# mcu.net
KiCad netlist of a schematic drawn in Altium Designer
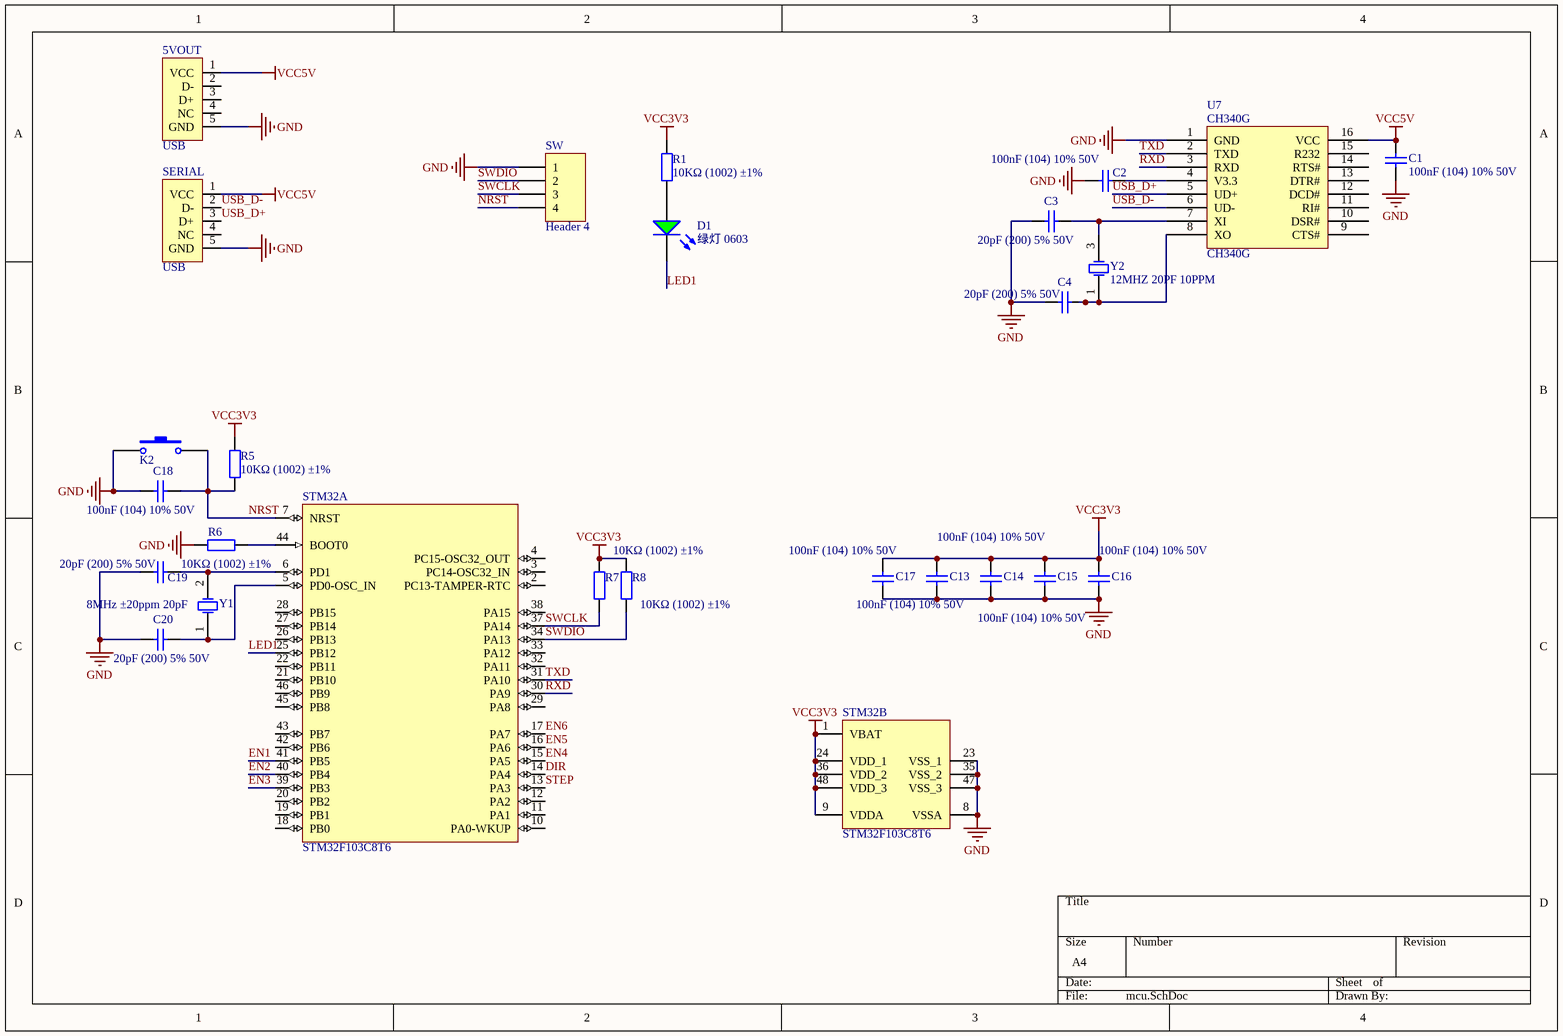
[diagram p0: mcu.SchDoc]

(export (version "E")
  (design (tool "Eeschema 10.0.6"))
  (components
    (comp (ref "5VOUT")
      (value "USB")
      (footprint "USB_5")
      (libsource (lib "Personal_Accumulation_Sch") (part "USB_2"))
    )
    (comp (ref "C1")
      (value "100nF (104) 10% 50V")
      (footprint "0603_C")
      (description "贴片电容")
      (libsource (lib "Miscellaneous Devices LC") (part "0603 100nF (104) 10% 50V"))
    )
    (comp (ref "C2")
      (value "100nF (104) 10% 50V")
      (footprint "0603_C")
      (description "贴片电容")
      (libsource (lib "Miscellaneous Devices LC") (part "0603 100nF (104) 10% 50V"))
    )
    (comp (ref "C3")
      (value "20pF (200) 5% 50V")
      (footprint "0603_C")
      (description "贴片电容")
      (libsource (lib "Miscellaneous Devices LC") (part "0603 20pF (200) 5% 50V"))
    )
    (comp (ref "C4")
      (value "20pF (200) 5% 50V")
      (footprint "0603_C")
      (description "贴片电容")
      (libsource (lib "Miscellaneous Devices LC") (part "0603 20pF (200) 5% 50V"))
    )
    (comp (ref "C13")
      (value "100nF (104) 10% 50V")
      (footprint "0603_C")
      (description "贴片电容")
      (libsource (lib "Miscellaneous Devices LC") (part "0603 100nF (104) 10% 50V"))
    )
    (comp (ref "C14")
      (value "100nF (104) 10% 50V")
      (footprint "0603_C")
      (description "贴片电容")
      (libsource (lib "Miscellaneous Devices LC") (part "0603 100nF (104) 10% 50V"))
    )
    (comp (ref "C15")
      (value "100nF (104) 10% 50V")
      (footprint "0603_C")
      (description "贴片电容")
      (libsource (lib "Miscellaneous Devices LC") (part "0603 100nF (104) 10% 50V"))
    )
    (comp (ref "C16")
      (value "100nF (104) 10% 50V")
      (footprint "0603_C")
      (description "贴片电容")
      (libsource (lib "Miscellaneous Devices LC") (part "0603 100nF (104) 10% 50V"))
    )
    (comp (ref "C17")
      (value "100nF (104) 10% 50V")
      (footprint "0603_C")
      (description "贴片电容")
      (libsource (lib "Miscellaneous Devices LC") (part "0603 100nF (104) 10% 50V"))
    )
    (comp (ref "C18")
      (value "100nF (104) 10% 50V")
      (footprint "0603_C")
      (description "贴片电容")
      (libsource (lib "Miscellaneous Devices LC") (part "0603 100nF (104) 10% 50V"))
    )
    (comp (ref "C19")
      (value "20pF (200) 5% 50V")
      (footprint "0603_C")
      (description "贴片电容")
      (libsource (lib "Miscellaneous Devices LC") (part "0603 20pF (200) 5% 50V"))
    )
    (comp (ref "C20")
      (value "20pF (200) 5% 50V")
      (footprint "0603_C")
      (description "贴片电容")
      (libsource (lib "Miscellaneous Devices LC") (part "0603 20pF (200) 5% 50V"))
    )
    (comp (ref "D1")
      (value "绿灯 0603")
      (footprint "0603_LED_S1")
      (description "发光二极管")
      (libsource (lib "Miscellaneous Devices LC") (part "0603 绿灯"))
    )
    (comp (ref "K2")
      (value "KEY")
      (footprint "Key_Sop")
      (description "贴片按键")
      (libsource (lib "Schlib1") (part "KEY_SOP"))
    )
    (comp (ref "R1")
      (value "10KΩ (1002) ±1%")
      (footprint "0603_R")
      (description "贴片电阻")
      (libsource (lib "Miscellaneous Devices LC") (part "0603 10KΩ (1002) 1%"))
    )
    (comp (ref "R5")
      (value "10KΩ (1002) ±1%")
      (footprint "0603_R")
      (description "贴片电阻")
      (libsource (lib "") (part "0603 10KΩ (1002) 1%_1"))
    )
    (comp (ref "R6")
      (value "10KΩ (1002) ±1%")
      (footprint "0603_R")
      (description "贴片电阻")
      (libsource (lib "") (part "0603 10KΩ (1002) 1%_2"))
    )
    (comp (ref "R7")
      (value "10KΩ (1002) ±1%")
      (footprint "0603_R")
      (description "贴片电阻")
      (libsource (lib "") (part "0603 10KΩ (1002) 1%_1"))
    )
    (comp (ref "R8")
      (value "10KΩ (1002) ±1%")
      (footprint "0603_R")
      (description "贴片电阻")
      (libsource (lib "") (part "0603 10KΩ (1002) 1%_1"))
    )
    (comp (ref "SERIAL")
      (value "USB")
      (footprint "USB_5")
      (libsource (lib "Personal_Accumulation_Sch") (part "USB_2"))
    )
    (comp (ref "STM32")
      (value "STM32F103C8T6")
      (footprint "LQFP-48_7x7x05P")
      (description "ARM")
      (libsource (lib "Miscellaneous Devices LC") (part "STM32F103C8T6"))
    )
    (comp (ref "SW")
      (value "Header 4")
      (footprint "HDR1X4")
      (description "Header, 4-Pin")
      (fields (field (name "PUBLISHER") "Altium Limited"))
      (libsource (lib "Common Headers") (part "Header 4"))
    )
    (comp (ref "U7")
      (value "CH340G")
      (footprint "SOIC-16_150mil")
      (description "USB")
      (libsource (lib "Miscellaneous Devices LC") (part "CH340G_[C14267]"))
    )
    (comp (ref "Y1")
      (value "8MHz ±20ppm 20pF")
      (footprint "SMD-5032_2P")
      (description "贴片晶振")
      (libsource (lib "Miscellaneous Devices LC") (part "SMD-5032_2P 8MHz 20ppm 20pF"))
    )
    (comp (ref "Y2")
      (value "12MHZ 20PF 10PPM")
      (footprint "SMD-3225_4P")
      (description "贴片晶振")
      (libsource (lib "Miscellaneous Devices LC") (part "SMD-3225_4P  12MHZ 20PF 10PPM"))
    )
  )
  (nets
    (net (code "1") (name "/DIR") (class "Default")
      (node (ref "STM32") (pin "14") (pinfunction "PA4_14") (pintype "bidirectional"))
    )
    (net (code "2") (name "/EN1") (class "Default")
      (node (ref "STM32") (pin "41") (pinfunction "PB5_41") (pintype "bidirectional"))
    )
    (net (code "3") (name "/EN2") (class "Default")
      (node (ref "STM32") (pin "40") (pinfunction "PB4_40") (pintype "bidirectional"))
    )
    (net (code "4") (name "/EN3") (class "Default")
      (node (ref "STM32") (pin "39") (pinfunction "PB3_39") (pintype "bidirectional"))
    )
    (net (code "5") (name "/EN4") (class "Default")
      (node (ref "STM32") (pin "15") (pinfunction "PA5_15") (pintype "bidirectional"))
    )
    (net (code "6") (name "/EN5") (class "Default")
      (node (ref "STM32") (pin "16") (pinfunction "PA6_16") (pintype "bidirectional"))
    )
    (net (code "7") (name "/EN6") (class "Default")
      (node (ref "STM32") (pin "17") (pinfunction "PA7_17") (pintype "bidirectional"))
    )
    (net (code "8") (name "/LED1") (class "Default")
      (node (ref "D1") (pin "K") (pinfunction "K_K") (pintype "passive"))
      (node (ref "STM32") (pin "25") (pinfunction "PB12_25") (pintype "bidirectional"))
    )
    (net (code "9") (name "/NRST") (class "Default")
      (node (ref "C18") (pin "1") (pinfunction "1_1") (pintype "passive"))
      (node (ref "K2") (pin "2") (pinfunction "2_2") (pintype "passive"))
      (node (ref "R5") (pin "1") (pinfunction "1_1") (pintype "passive"))
      (node (ref "STM32") (pin "7") (pinfunction "NRST_7") (pintype "bidirectional"))
      (node (ref "SW") (pin "4") (pinfunction "4_4") (pintype "passive"))
    )
    (net (code "10") (name "/RXD") (class "Default")
      (node (ref "STM32") (pin "30") (pinfunction "PA9_30") (pintype "bidirectional"))
      (node (ref "U7") (pin "3") (pinfunction "RXD_3") (pintype "passive"))
    )
    (net (code "11") (name "/STEP") (class "Default")
      (node (ref "STM32") (pin "13") (pinfunction "PA3_13") (pintype "bidirectional"))
    )
    (net (code "12") (name "/SWCLK") (class "Default")
      (node (ref "R7") (pin "1") (pinfunction "1_1") (pintype "passive"))
      (node (ref "STM32") (pin "37") (pinfunction "PA14_37") (pintype "bidirectional"))
      (node (ref "SW") (pin "3") (pinfunction "3_3") (pintype "passive"))
    )
    (net (code "13") (name "/SWDIO") (class "Default")
      (node (ref "R8") (pin "1") (pinfunction "1_1") (pintype "passive"))
      (node (ref "STM32") (pin "34") (pinfunction "PA13_34") (pintype "bidirectional"))
      (node (ref "SW") (pin "2") (pinfunction "2_2") (pintype "passive"))
    )
    (net (code "14") (name "/TXD") (class "Default")
      (node (ref "STM32") (pin "31") (pinfunction "PA10_31") (pintype "bidirectional"))
      (node (ref "U7") (pin "2") (pinfunction "TXD_2") (pintype "passive"))
    )
    (net (code "15") (name "/USB_D+") (class "Default")
      (node (ref "SERIAL") (pin "3") (pinfunction "D+_3") (pintype "passive"))
      (node (ref "U7") (pin "5") (pinfunction "UD+_5") (pintype "passive"))
    )
    (net (code "16") (name "/USB_D-") (class "Default")
      (node (ref "SERIAL") (pin "2") (pinfunction "D-_2") (pintype "passive"))
      (node (ref "U7") (pin "6") (pinfunction "UD-_6") (pintype "passive"))
    )
    (net (code "17") (name "GND") (class "Default")
      (node (ref "5VOUT") (pin "5") (pinfunction "GND_5") (pintype "passive"))
      (node (ref "C1") (pin "1") (pinfunction "1_1") (pintype "passive"))
      (node (ref "C13") (pin "1") (pinfunction "1_1") (pintype "passive"))
      (node (ref "C14") (pin "1") (pinfunction "1_1") (pintype "passive"))
      (node (ref "C15") (pin "1") (pinfunction "1_1") (pintype "passive"))
      (node (ref "C16") (pin "1") (pinfunction "1_1") (pintype "passive"))
      (node (ref "C17") (pin "1") (pinfunction "1_1") (pintype "passive"))
      (node (ref "C18") (pin "2") (pinfunction "2_2") (pintype "passive"))
      (node (ref "C19") (pin "1") (pinfunction "1_1") (pintype "passive"))
      (node (ref "C2") (pin "1") (pinfunction "1_1") (pintype "passive"))
      (node (ref "C20") (pin "1") (pinfunction "1_1") (pintype "passive"))
      (node (ref "C3") (pin "2") (pinfunction "2_2") (pintype "passive"))
      (node (ref "C4") (pin "2") (pinfunction "2_2") (pintype "passive"))
      (node (ref "K2") (pin "1") (pinfunction "1_1") (pintype "passive"))
      (node (ref "R6") (pin "2") (pinfunction "2_2") (pintype "passive"))
      (node (ref "SERIAL") (pin "5") (pinfunction "GND_5") (pintype "passive"))
      (node (ref "STM32") (pin "23") (pinfunction "VSS_1_23") (pintype "power_in"))
      (node (ref "STM32") (pin "35") (pinfunction "VSS_2_35") (pintype "power_in"))
      (node (ref "STM32") (pin "47") (pinfunction "VSS_3_47") (pintype "power_in"))
      (node (ref "STM32") (pin "8") (pinfunction "VSSA_8") (pintype "power_in"))
      (node (ref "SW") (pin "1") (pinfunction "1_1") (pintype "passive"))
      (node (ref "U7") (pin "1") (pinfunction "GND_1") (pintype "passive"))
    )
    (net (code "18") (name "Net-(D1-PadA)") (class "Default")
      (node (ref "D1") (pin "A") (pinfunction "A_A") (pintype "passive"))
      (node (ref "R1") (pin "2") (pinfunction "2_2") (pintype "passive"))
    )
    (net (code "19") (name "Net-(STM32A-BOOT0)") (class "Default")
      (node (ref "R6") (pin "1") (pinfunction "1_1") (pintype "passive"))
      (node (ref "STM32") (pin "44") (pinfunction "BOOT0_44") (pintype "input"))
    )
    (net (code "20") (name "Net-(STM32A-PD0-OSC_IN)") (class "Default")
      (node (ref "C20") (pin "2") (pinfunction "2_2") (pintype "passive"))
      (node (ref "STM32") (pin "5") (pinfunction "PD0-OSC_IN_5") (pintype "bidirectional"))
      (node (ref "Y1") (pin "1") (pinfunction "OSC1_1") (pintype "passive"))
    )
    (net (code "21") (name "Net-(STM32A-PD1)") (class "Default")
      (node (ref "C19") (pin "2") (pinfunction "2_2") (pintype "passive"))
      (node (ref "STM32") (pin "6") (pinfunction "PD1_6") (pintype "bidirectional"))
      (node (ref "Y1") (pin "2") (pinfunction "OSC2_2") (pintype "passive"))
    )
    (net (code "22") (name "Net-(U7-V3.3)") (class "Default")
      (node (ref "C2") (pin "2") (pinfunction "2_2") (pintype "passive"))
      (node (ref "U7") (pin "4") (pinfunction "V3.3_4") (pintype "passive"))
    )
    (net (code "23") (name "Net-(U7-XI)") (class "Default")
      (node (ref "C3") (pin "1") (pinfunction "1_1") (pintype "passive"))
      (node (ref "U7") (pin "7") (pinfunction "XI_7") (pintype "passive"))
      (node (ref "Y2") (pin "3") (pinfunction "OSC2_3") (pintype "passive"))
    )
    (net (code "24") (name "Net-(U7-XO)") (class "Default")
      (node (ref "C4") (pin "1") (pinfunction "1_1") (pintype "passive"))
      (node (ref "U7") (pin "8") (pinfunction "XO_8") (pintype "passive"))
      (node (ref "Y2") (pin "1") (pinfunction "OSC1_1") (pintype "passive"))
    )
    (net (code "25") (name "VCC3V3") (class "Default")
      (node (ref "C13") (pin "2") (pinfunction "2_2") (pintype "passive"))
      (node (ref "C14") (pin "2") (pinfunction "2_2") (pintype "passive"))
      (node (ref "C15") (pin "2") (pinfunction "2_2") (pintype "passive"))
      (node (ref "C16") (pin "2") (pinfunction "2_2") (pintype "passive"))
      (node (ref "C17") (pin "2") (pinfunction "2_2") (pintype "passive"))
      (node (ref "R1") (pin "1") (pinfunction "1_1") (pintype "passive"))
      (node (ref "R5") (pin "2") (pinfunction "2_2") (pintype "passive"))
      (node (ref "R7") (pin "2") (pinfunction "2_2") (pintype "passive"))
      (node (ref "R8") (pin "2") (pinfunction "2_2") (pintype "passive"))
      (node (ref "STM32") (pin "1") (pinfunction "VBAT_1") (pintype "power_in"))
      (node (ref "STM32") (pin "24") (pinfunction "VDD_1_24") (pintype "power_in"))
      (node (ref "STM32") (pin "36") (pinfunction "VDD_2_36") (pintype "power_in"))
      (node (ref "STM32") (pin "48") (pinfunction "VDD_3_48") (pintype "power_in"))
      (node (ref "STM32") (pin "9") (pinfunction "VDDA_9") (pintype "power_in"))
    )
    (net (code "26") (name "VCC5V") (class "Default")
      (node (ref "5VOUT") (pin "1") (pinfunction "VCC_1") (pintype "passive"))
      (node (ref "C1") (pin "2") (pinfunction "2_2") (pintype "passive"))
      (node (ref "SERIAL") (pin "1") (pinfunction "VCC_1") (pintype "passive"))
      (node (ref "U7") (pin "16") (pinfunction "VCC_16") (pintype "passive"))
    )
    (net (code "27") (name "unconnected-(5VOUT-D+-Pad3)") (class "Default")
      (node (ref "5VOUT") (pin "3") (pinfunction "D+_3") (pintype "passive"))
    )
    (net (code "28") (name "unconnected-(5VOUT-D--Pad2)") (class "Default")
      (node (ref "5VOUT") (pin "2") (pinfunction "D-_2") (pintype "passive"))
    )
    (net (code "29") (name "unconnected-(5VOUT-NC-Pad4)") (class "Default")
      (node (ref "5VOUT") (pin "4") (pinfunction "NC_4") (pintype "passive"))
    )
    (net (code "30") (name "unconnected-(SERIAL-NC-Pad4)") (class "Default")
      (node (ref "SERIAL") (pin "4") (pinfunction "NC_4") (pintype "passive"))
    )
    (net (code "31") (name "unconnected-(STM32A-PA0-WKUP-Pad10)") (class "Default")
      (node (ref "STM32") (pin "10") (pinfunction "PA0-WKUP_10") (pintype "bidirectional"))
    )
    (net (code "32") (name "unconnected-(STM32A-PA1-Pad11)") (class "Default")
      (node (ref "STM32") (pin "11") (pinfunction "PA1_11") (pintype "bidirectional"))
    )
    (net (code "33") (name "unconnected-(STM32A-PA2-Pad12)") (class "Default")
      (node (ref "STM32") (pin "12") (pinfunction "PA2_12") (pintype "bidirectional"))
    )
    (net (code "34") (name "unconnected-(STM32A-PA8-Pad29)") (class "Default")
      (node (ref "STM32") (pin "29") (pinfunction "PA8_29") (pintype "bidirectional"))
    )
    (net (code "35") (name "unconnected-(STM32A-PA11-Pad32)") (class "Default")
      (node (ref "STM32") (pin "32") (pinfunction "PA11_32") (pintype "bidirectional"))
    )
    (net (code "36") (name "unconnected-(STM32A-PA12-Pad33)") (class "Default")
      (node (ref "STM32") (pin "33") (pinfunction "PA12_33") (pintype "bidirectional"))
    )
    (net (code "37") (name "unconnected-(STM32A-PA15-Pad38)") (class "Default")
      (node (ref "STM32") (pin "38") (pinfunction "PA15_38") (pintype "bidirectional"))
    )
    (net (code "38") (name "unconnected-(STM32A-PB0-Pad18)") (class "Default")
      (node (ref "STM32") (pin "18") (pinfunction "PB0_18") (pintype "bidirectional"))
    )
    (net (code "39") (name "unconnected-(STM32A-PB1-Pad19)") (class "Default")
      (node (ref "STM32") (pin "19") (pinfunction "PB1_19") (pintype "bidirectional"))
    )
    (net (code "40") (name "unconnected-(STM32A-PB2-Pad20)") (class "Default")
      (node (ref "STM32") (pin "20") (pinfunction "PB2_20") (pintype "bidirectional"))
    )
    (net (code "41") (name "unconnected-(STM32A-PB6-Pad42)") (class "Default")
      (node (ref "STM32") (pin "42") (pinfunction "PB6_42") (pintype "bidirectional"))
    )
    (net (code "42") (name "unconnected-(STM32A-PB7-Pad43)") (class "Default")
      (node (ref "STM32") (pin "43") (pinfunction "PB7_43") (pintype "bidirectional"))
    )
    (net (code "43") (name "unconnected-(STM32A-PB8-Pad45)") (class "Default")
      (node (ref "STM32") (pin "45") (pinfunction "PB8_45") (pintype "bidirectional"))
    )
    (net (code "44") (name "unconnected-(STM32A-PB9-Pad46)") (class "Default")
      (node (ref "STM32") (pin "46") (pinfunction "PB9_46") (pintype "bidirectional"))
    )
    (net (code "45") (name "unconnected-(STM32A-PB10-Pad21)") (class "Default")
      (node (ref "STM32") (pin "21") (pinfunction "PB10_21") (pintype "bidirectional"))
    )
    (net (code "46") (name "unconnected-(STM32A-PB11-Pad22)") (class "Default")
      (node (ref "STM32") (pin "22") (pinfunction "PB11_22") (pintype "bidirectional"))
    )
    (net (code "47") (name "unconnected-(STM32A-PB13-Pad26)") (class "Default")
      (node (ref "STM32") (pin "26") (pinfunction "PB13_26") (pintype "bidirectional"))
    )
    (net (code "48") (name "unconnected-(STM32A-PB14-Pad27)") (class "Default")
      (node (ref "STM32") (pin "27") (pinfunction "PB14_27") (pintype "bidirectional"))
    )
    (net (code "49") (name "unconnected-(STM32A-PB15-Pad28)") (class "Default")
      (node (ref "STM32") (pin "28") (pinfunction "PB15_28") (pintype "bidirectional"))
    )
    (net (code "50") (name "unconnected-(STM32A-PC13-TAMPER-RTC-Pad2)") (class "Default")
      (node (ref "STM32") (pin "2") (pinfunction "PC13-TAMPER-RTC_2") (pintype "bidirectional"))
    )
    (net (code "51") (name "unconnected-(STM32A-PC14-OSC32_IN-Pad3)") (class "Default")
      (node (ref "STM32") (pin "3") (pinfunction "PC14-OSC32_IN_3") (pintype "bidirectional"))
    )
    (net (code "52") (name "unconnected-(STM32A-PC15-OSC32_OUT-Pad4)") (class "Default")
      (node (ref "STM32") (pin "4") (pinfunction "PC15-OSC32_OUT_4") (pintype "bidirectional"))
    )
    (net (code "53") (name "unconnected-(U7-CTS#-Pad9)") (class "Default")
      (node (ref "U7") (pin "9") (pinfunction "CTS#_9") (pintype "passive"))
    )
    (net (code "54") (name "unconnected-(U7-DCD#-Pad12)") (class "Default")
      (node (ref "U7") (pin "12") (pinfunction "DCD#_12") (pintype "passive"))
    )
    (net (code "55") (name "unconnected-(U7-DSR#-Pad10)") (class "Default")
      (node (ref "U7") (pin "10") (pinfunction "DSR#_10") (pintype "passive"))
    )
    (net (code "56") (name "unconnected-(U7-DTR#-Pad13)") (class "Default")
      (node (ref "U7") (pin "13") (pinfunction "DTR#_13") (pintype "passive"))
    )
    (net (code "57") (name "unconnected-(U7-R232-Pad15)") (class "Default")
      (node (ref "U7") (pin "15") (pinfunction "R232_15") (pintype "passive"))
    )
    (net (code "58") (name "unconnected-(U7-RI#-Pad11)") (class "Default")
      (node (ref "U7") (pin "11") (pinfunction "RI#_11") (pintype "passive"))
    )
    (net (code "59") (name "unconnected-(U7-RTS#-Pad14)") (class "Default")
      (node (ref "U7") (pin "14") (pinfunction "RTS#_14") (pintype "passive"))
    )
  )
)
